# Voltage_input.net
KiCad netlist of a schematic drawn in Altium Designer
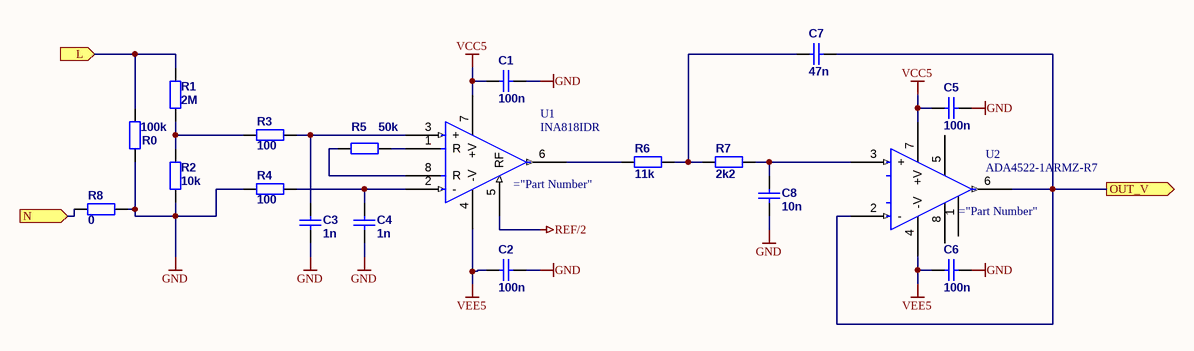
[diagram p0: Voltage input.SchDoc]

(export (version "E")
  (design (tool "Eeschema 10.0.6"))
  (components
    (comp (ref "C1")
      (value "100n")
      (footprint "C0805")
      (description "Capacitor")
      (libsource (lib "capacitors") (part "Cap"))
    )
    (comp (ref "C2")
      (value "100n")
      (footprint "C0805")
      (description "Capacitor")
      (libsource (lib "capacitors") (part "Cap"))
    )
    (comp (ref "C3")
      (value "1n")
      (footprint "C1206")
      (description "Capacitor")
      (libsource (lib "capacitors") (part "Cap"))
    )
    (comp (ref "C4")
      (value "1n")
      (footprint "C1206")
      (description "Capacitor")
      (libsource (lib "capacitors") (part "Cap"))
    )
    (comp (ref "C5")
      (value "100n")
      (footprint "C0805")
      (description "Capacitor")
      (libsource (lib "capacitors") (part "Cap"))
    )
    (comp (ref "C6")
      (value "100n")
      (footprint "C0805")
      (description "Capacitor")
      (libsource (lib "capacitors") (part "Cap"))
    )
    (comp (ref "C7")
      (value "47n")
      (footprint "C0805")
      (description "Capacitor")
      (libsource (lib "capacitors") (part "Cap"))
    )
    (comp (ref "C8")
      (value "10n")
      (footprint "C0805")
      (description "Capacitor")
      (libsource (lib "capacitors") (part "Cap"))
    )
    (comp (ref "R0")
      (value "100k")
      (footprint "R2512")
      (description "Resistor")
      (libsource (lib "") (part "Res_2"))
    )
    (comp (ref "R1")
      (value "2M")
      (footprint "R1206")
      (description "Resistor")
      (libsource (lib "resistors") (part "Res"))
    )
    (comp (ref "R2")
      (value "10k")
      (footprint "R1206")
      (description "Resistor")
      (libsource (lib "resistors") (part "Res"))
    )
    (comp (ref "R3")
      (value "100")
      (footprint "R1206")
      (description "Resistor")
      (libsource (lib "") (part "Res_1"))
    )
    (comp (ref "R4")
      (value "100")
      (footprint "R1206")
      (description "Resistor")
      (libsource (lib "") (part "Res_1"))
    )
    (comp (ref "R5")
      (value "50k")
      (footprint "R0805")
      (description "Resistor")
      (libsource (lib "") (part "Res_1"))
    )
    (comp (ref "R6")
      (value "11k")
      (footprint "R0805")
      (description "Resistor")
      (libsource (lib "") (part "Res_1"))
    )
    (comp (ref "R7")
      (value "2k2")
      (footprint "R0805")
      (description "Resistor")
      (libsource (lib "") (part "Res_1"))
    )
    (comp (ref "R8")
      (value "0")
      (footprint "R1206")
      (description "Resistor")
      (libsource (lib "") (part "Res_1"))
    )
    (comp (ref "U1")
      (value "INA818IDR")
      (footprint "SOIC-8_TEX")
      (description "No Description Available")
      (fields (field (name "COPYRIGHT") "Copyright (C) 2021 Ultra Librarian. All rights reserved."))
      (libsource (lib "RS_Opamps") (part "INA818IDR"))
    )
    (comp (ref "U2")
      (value "ADA4522-1ARMZ-R7")
      (footprint "Analog_Devices_RM-8_IPC_C")
      (libsource (lib "RS_Opamps") (part "ADA4522-1ARMZ-R7"))
    )
  )
  (nets
    (net (code "1") (name "/L") (class "Default")
      (node (ref "R0") (pin "2") (pinfunction "2_2") (pintype "passive"))
      (node (ref "R1") (pin "1") (pinfunction "1_1") (pintype "passive"))
    )
    (net (code "2") (name "/N") (class "Default")
      (node (ref "R8") (pin "1") (pinfunction "1_1") (pintype "passive"))
    )
    (net (code "3") (name "/OUT_V") (class "Default")
      (node (ref "C7") (pin "1") (pinfunction "1_1") (pintype "passive"))
      (node (ref "U2") (pin "2") (pinfunction "-_2") (pintype "input"))
      (node (ref "U2") (pin "6") (pinfunction "OUT_6") (pintype "output"))
    )
    (net (code "4") (name "GND") (class "Default")
      (node (ref "C1") (pin "2") (pinfunction "2_2") (pintype "passive"))
      (node (ref "C2") (pin "1") (pinfunction "1_1") (pintype "passive"))
      (node (ref "C3") (pin "1") (pinfunction "1_1") (pintype "passive"))
      (node (ref "C4") (pin "1") (pinfunction "1_1") (pintype "passive"))
      (node (ref "C5") (pin "1") (pinfunction "1_1") (pintype "passive"))
      (node (ref "C6") (pin "2") (pinfunction "2_2") (pintype "passive"))
      (node (ref "C8") (pin "2") (pinfunction "2_2") (pintype "passive"))
      (node (ref "R0") (pin "1") (pinfunction "1_1") (pintype "passive"))
      (node (ref "R2") (pin "2") (pinfunction "2_2") (pintype "passive"))
      (node (ref "R4") (pin "1") (pinfunction "1_1") (pintype "passive"))
      (node (ref "R8") (pin "2") (pinfunction "2_2") (pintype "passive"))
    )
    (net (code "5") (name "Net-(C7-Pad2)") (class "Default")
      (node (ref "C7") (pin "2") (pinfunction "2_2") (pintype "passive"))
      (node (ref "R6") (pin "2") (pinfunction "2_2") (pintype "passive"))
      (node (ref "R7") (pin "1") (pinfunction "1_1") (pintype "passive"))
    )
    (net (code "6") (name "Net-(R1-Pad2)") (class "Default")
      (node (ref "R1") (pin "2") (pinfunction "2_2") (pintype "passive"))
      (node (ref "R2") (pin "1") (pinfunction "1_1") (pintype "passive"))
      (node (ref "R3") (pin "1") (pinfunction "1_1") (pintype "passive"))
    )
    (net (code "7") (name "Net-(R5-Pad1)") (class "Default")
      (node (ref "R5") (pin "1") (pinfunction "1_1") (pintype "passive"))
      (node (ref "U1") (pin "8") (pinfunction "R_8") (pintype "passive"))
    )
    (net (code "8") (name "Net-(R5-Pad2)") (class "Default")
      (node (ref "R5") (pin "2") (pinfunction "2_2") (pintype "passive"))
      (node (ref "U1") (pin "1") (pinfunction "R_1") (pintype "passive"))
    )
    (net (code "9") (name "Net-(U1-+)") (class "Default")
      (node (ref "C3") (pin "2") (pinfunction "2_2") (pintype "passive"))
      (node (ref "R3") (pin "2") (pinfunction "2_2") (pintype "passive"))
      (node (ref "U1") (pin "3") (pinfunction "+_3") (pintype "input"))
    )
    (net (code "10") (name "Net-(U1--)") (class "Default")
      (node (ref "C4") (pin "2") (pinfunction "2_2") (pintype "passive"))
      (node (ref "R4") (pin "2") (pinfunction "2_2") (pintype "passive"))
      (node (ref "U1") (pin "2") (pinfunction "-_2") (pintype "input"))
    )
    (net (code "11") (name "Net-(U1-OUT)") (class "Default")
      (node (ref "R6") (pin "1") (pinfunction "1_1") (pintype "passive"))
      (node (ref "U1") (pin "6") (pinfunction "OUT_6") (pintype "output"))
    )
    (net (code "12") (name "Net-(U2-+)") (class "Default")
      (node (ref "C8") (pin "1") (pinfunction "1_1") (pintype "passive"))
      (node (ref "R7") (pin "2") (pinfunction "2_2") (pintype "passive"))
      (node (ref "U2") (pin "3") (pinfunction "+_3") (pintype "input"))
    )
    (net (code "13") (name "REF{slash}2") (class "Default")
      (node (ref "U1") (pin "5") (pinfunction "RF_5") (pintype "input"))
    )
    (net (code "14") (name "VCC5") (class "Default")
      (node (ref "C1") (pin "1") (pinfunction "1_1") (pintype "passive"))
      (node (ref "C5") (pin "2") (pinfunction "2_2") (pintype "passive"))
      (node (ref "U1") (pin "7") (pinfunction "+V_7") (pintype "passive"))
      (node (ref "U2") (pin "7") (pinfunction "+V_7") (pintype "passive"))
    )
    (net (code "15") (name "VEE5") (class "Default")
      (node (ref "C2") (pin "2") (pinfunction "2_2") (pintype "passive"))
      (node (ref "C6") (pin "1") (pinfunction "1_1") (pintype "passive"))
      (node (ref "U1") (pin "4") (pinfunction "-V_4") (pintype "passive"))
      (node (ref "U2") (pin "4") (pinfunction "-V_4") (pintype "passive"))
    )
    (net (code "16") (name "unconnected-(U2-Pad1)") (class "Default")
      (node (ref "U2") (pin "1") (pintype "passive"))
    )
    (net (code "17") (name "unconnected-(U2-Pad5)") (class "Default")
      (node (ref "U2") (pin "5") (pintype "passive"))
    )
    (net (code "18") (name "unconnected-(U2-Pad8)") (class "Default")
      (node (ref "U2") (pin "8") (pintype "passive"))
    )
  )
)
